# sqare_inch_challenge.net
KiCad netlist of a schematic drawn in EAGLE
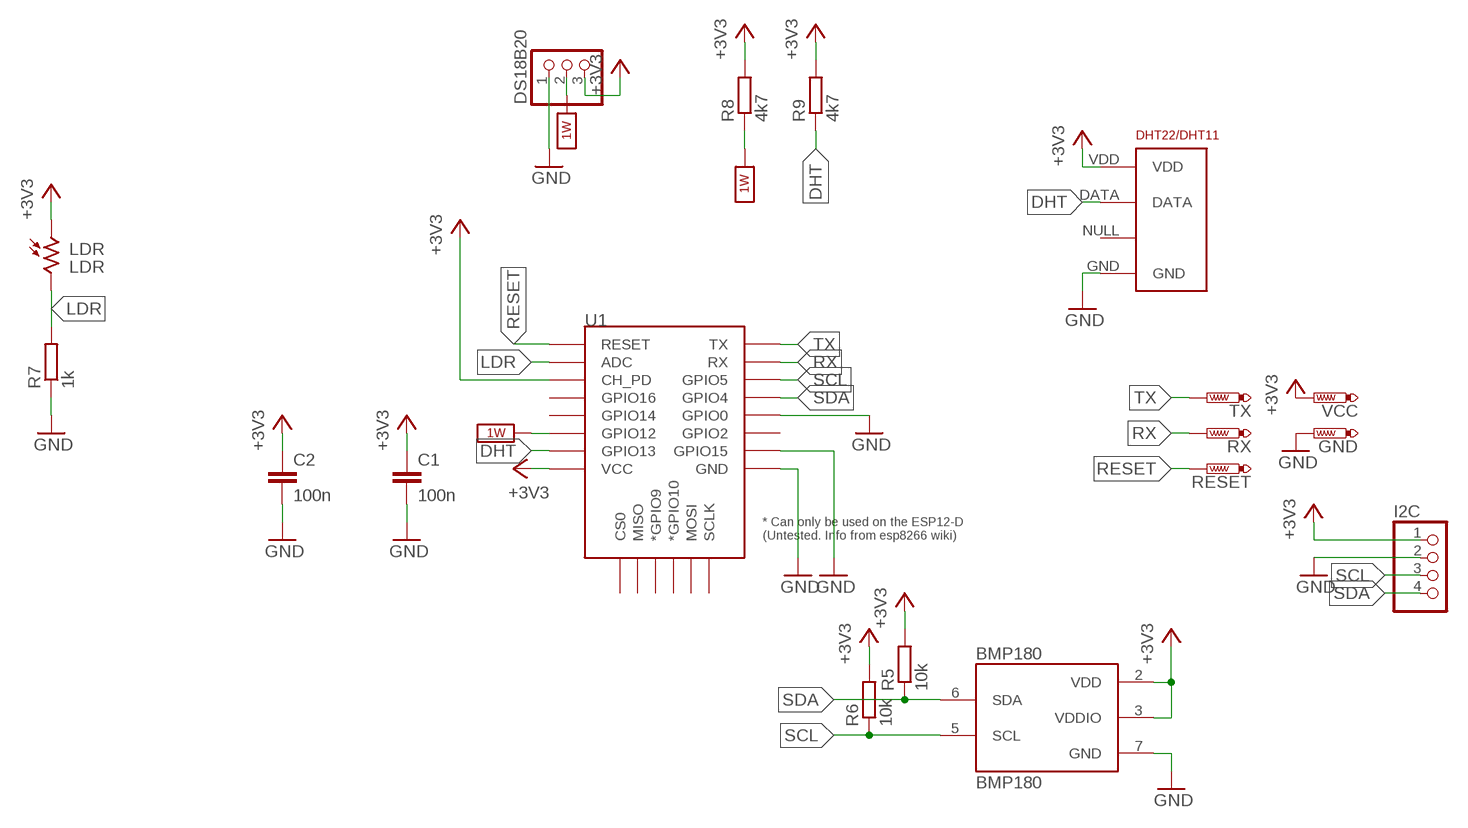
[diagram p0: schematic, sheet 1]

(export (version "E")
  (design (tool "Eeschema 10.0.6"))
  (components
    (comp (ref "BMP180")
      (value "BMP180")
      (footprint "eagle-import:BMP180")
      (libsource (lib "eagle-import") (part "BMP180"))
    )
    (comp (ref "C1")
      (value "100n")
      (footprint "eagle-import:C0805")
      (libsource (lib "eagle-import") (part "C-EUC0805"))
    )
    (comp (ref "C2")
      (value "100n")
      (footprint "eagle-import:C0805")
      (libsource (lib "eagle-import") (part "C-EUC0805"))
    )
    (comp (ref "DHT22/DHT11")
      (value "RHT03_DHT-22_AM2302")
      (footprint "eagle-import:RHT03_DHT-22")
      (libsource (lib "eagle-import") (part "RHT03_DHT-22_AM2302"))
    )
    (comp (ref "DS18B20")
      (value "PINHD-1X3")
      (footprint "eagle-import:1X03")
      (libsource (lib "eagle-import") (part "PINHD-1X3"))
    )
    (comp (ref "GND")
      (value "GND")
      (footprint "eagle-import:TP17SQ")
      (libsource (lib "eagle-import") (part "PTR1TP17SQ"))
    )
    (comp (ref "I2C")
      (value "PINHD-1X4")
      (footprint "eagle-import:1X04")
      (libsource (lib "eagle-import") (part "PINHD-1X4"))
    )
    (comp (ref "LDR")
      (value "LDR")
      (footprint "eagle-import:T0-46-A10XX")
      (libsource (lib "eagle-import") (part "A1050_13"))
    )
    (comp (ref "R5")
      (value "10k")
      (footprint "eagle-import:R0805")
      (libsource (lib "eagle-import") (part "R-EU_R0805"))
    )
    (comp (ref "R6")
      (value "10k")
      (footprint "eagle-import:R0805")
      (libsource (lib "eagle-import") (part "R-EU_R0805"))
    )
    (comp (ref "R7")
      (value "1k")
      (footprint "eagle-import:R0805")
      (libsource (lib "eagle-import") (part "R-EU_R0805"))
    )
    (comp (ref "R8")
      (value "4k7")
      (footprint "eagle-import:R0805")
      (libsource (lib "eagle-import") (part "R-EU_R0805"))
    )
    (comp (ref "R9")
      (value "4k7")
      (footprint "eagle-import:R0805")
      (libsource (lib "eagle-import") (part "R-EU_R0805"))
    )
    (comp (ref "RESET")
      (value "PTR1TP17SQ")
      (footprint "eagle-import:TP17SQ")
      (libsource (lib "eagle-import") (part "PTR1TP17SQ"))
    )
    (comp (ref "RX")
      (value "PTR1TP17SQ")
      (footprint "eagle-import:TP17SQ")
      (libsource (lib "eagle-import") (part "PTR1TP17SQ"))
    )
    (comp (ref "TX")
      (value "PTR1TP17SQ")
      (footprint "eagle-import:TP17SQ")
      (libsource (lib "eagle-import") (part "PTR1TP17SQ"))
    )
    (comp (ref "U1")
      (value "ESP12ESMD")
      (footprint "eagle-import:ESP12E-SMD")
      (libsource (lib "eagle-import") (part "ESP12ESMD"))
    )
    (comp (ref "VCC")
      (value "+3V3")
      (footprint "eagle-import:TP17SQ")
      (libsource (lib "eagle-import") (part "PTR1TP17SQ"))
    )
  )
  (nets
    (net (code "1") (name "+3V3") (class "Default")
      (node (ref "BMP180") (pin "2") (pinfunction "VDD_2") (pintype "power_in"))
      (node (ref "BMP180") (pin "3") (pinfunction "VDDIO_3") (pintype "power_in"))
      (node (ref "C1") (pin "1") (pinfunction "1_1") (pintype "passive"))
      (node (ref "C2") (pin "1") (pinfunction "1_1") (pintype "passive"))
      (node (ref "DHT22/DHT11") (pin "VDD") (pinfunction "VDD_VDD") (pintype "power_in"))
      (node (ref "DS18B20") (pin "3") (pinfunction "3_3") (pintype "passive"))
      (node (ref "I2C") (pin "1") (pinfunction "1_1") (pintype "passive"))
      (node (ref "LDR") (pin "1") (pinfunction "1_1") (pintype "passive"))
      (node (ref "R5") (pin "2") (pinfunction "2_2") (pintype "passive"))
      (node (ref "R6") (pin "2") (pinfunction "2_2") (pintype "passive"))
      (node (ref "R8") (pin "2") (pinfunction "2_2") (pintype "passive"))
      (node (ref "R9") (pin "2") (pinfunction "2_2") (pintype "passive"))
      (node (ref "U1") (pin "CH_PD") (pinfunction "CH_PD_CH_PD") (pintype "bidirectional"))
      (node (ref "U1") (pin "VCC") (pinfunction "VCC_VCC") (pintype "bidirectional"))
      (node (ref "VCC") (pin "TP") (pinfunction "TP_TP") (pintype "input"))
    )
    (net (code "2") (name "1W_SUP") (class "Default")
      (node (ref "DS18B20") (pin "2") (pinfunction "2_2") (pintype "passive"))
      (node (ref "R8") (pin "1") (pinfunction "1_1") (pintype "passive"))
      (node (ref "U1") (pin "GPIO12") (pinfunction "GPIO12_GPIO12") (pintype "bidirectional"))
    )
    (net (code "3") (name "DHT") (class "Default")
      (node (ref "DHT22/DHT11") (pin "DATA") (pinfunction "DATA_DATA") (pintype "bidirectional"))
      (node (ref "R9") (pin "1") (pinfunction "1_1") (pintype "passive"))
      (node (ref "U1") (pin "GPIO13") (pinfunction "GPIO13_GPIO13") (pintype "bidirectional"))
    )
    (net (code "4") (name "GND") (class "Default")
      (node (ref "BMP180") (pin "7") (pinfunction "GND_7") (pintype "power_in"))
      (node (ref "C1") (pin "2") (pinfunction "2_2") (pintype "passive"))
      (node (ref "C2") (pin "2") (pinfunction "2_2") (pintype "passive"))
      (node (ref "DHT22/DHT11") (pin "GND") (pinfunction "GND_GND") (pintype "power_in"))
      (node (ref "DS18B20") (pin "1") (pinfunction "1_1") (pintype "passive"))
      (node (ref "GND") (pin "TP") (pinfunction "TP_TP") (pintype "input"))
      (node (ref "I2C") (pin "2") (pinfunction "2_2") (pintype "passive"))
      (node (ref "R7") (pin "1") (pinfunction "1_1") (pintype "passive"))
      (node (ref "U1") (pin "GND") (pinfunction "GND_GND") (pintype "bidirectional"))
      (node (ref "U1") (pin "GPIO0") (pinfunction "GPIO0_GPIO0") (pintype "bidirectional"))
      (node (ref "U1") (pin "GPIO15") (pinfunction "GPIO15_GPIO15") (pintype "bidirectional"))
    )
    (net (code "5") (name "LDR") (class "Default")
      (node (ref "LDR") (pin "2") (pinfunction "2_2") (pintype "passive"))
      (node (ref "R7") (pin "2") (pinfunction "2_2") (pintype "passive"))
      (node (ref "U1") (pin "ADC") (pinfunction "ADC_ADC") (pintype "bidirectional"))
    )
    (net (code "6") (name "RESET") (class "Default")
      (node (ref "RESET") (pin "TP") (pinfunction "TP_TP") (pintype "input"))
      (node (ref "U1") (pin "RESET") (pinfunction "RESET_RESET") (pintype "bidirectional"))
    )
    (net (code "7") (name "RX") (class "Default")
      (node (ref "RX") (pin "TP") (pinfunction "TP_TP") (pintype "input"))
      (node (ref "U1") (pin "RXD0") (pinfunction "RX_RXD0") (pintype "bidirectional"))
    )
    (net (code "8") (name "SCL") (class "Default")
      (node (ref "BMP180") (pin "5") (pinfunction "SCL_5") (pintype "input"))
      (node (ref "I2C") (pin "3") (pinfunction "3_3") (pintype "passive"))
      (node (ref "R6") (pin "1") (pinfunction "1_1") (pintype "passive"))
      (node (ref "U1") (pin "GPIO5") (pinfunction "GPIO5_GPIO5") (pintype "bidirectional"))
    )
    (net (code "9") (name "SDA") (class "Default")
      (node (ref "BMP180") (pin "6") (pinfunction "SDA_6") (pintype "bidirectional"))
      (node (ref "I2C") (pin "4") (pinfunction "4_4") (pintype "passive"))
      (node (ref "R5") (pin "1") (pinfunction "1_1") (pintype "passive"))
      (node (ref "U1") (pin "GPIO4") (pinfunction "GPIO4_GPIO4") (pintype "bidirectional"))
    )
    (net (code "10") (name "TX") (class "Default")
      (node (ref "TX") (pin "TP") (pinfunction "TP_TP") (pintype "input"))
      (node (ref "U1") (pin "TXD0") (pinfunction "TX_TXD0") (pintype "bidirectional"))
    )
    (net (code "11") (name "unconnected-(DHT22/DHT11-PadNULL)") (class "Default")
      (node (ref "DHT22/DHT11") (pin "NULL") (pinfunction "NULL_NULL") (pintype "no_connect"))
    )
    (net (code "12") (name "unconnected-(U1-*GPIO9-PadGPIO9)") (class "Default")
      (node (ref "U1") (pin "GPIO9") (pinfunction "*GPIO9_GPIO9") (pintype "bidirectional"))
    )
    (net (code "13") (name "unconnected-(U1-*GPIO10-PadGPIO10)") (class "Default")
      (node (ref "U1") (pin "GPIO10") (pinfunction "*GPIO10_GPIO10") (pintype "bidirectional"))
    )
    (net (code "14") (name "unconnected-(U1-PadCS0)") (class "Default")
      (node (ref "U1") (pin "CS0") (pinfunction "CS0_CS0") (pintype "bidirectional"))
    )
    (net (code "15") (name "unconnected-(U1-PadGPIO2)") (class "Default")
      (node (ref "U1") (pin "GPIO2") (pinfunction "GPIO2_GPIO2") (pintype "bidirectional"))
    )
    (net (code "16") (name "unconnected-(U1-PadGPIO14)") (class "Default")
      (node (ref "U1") (pin "GPIO14") (pinfunction "GPIO14_GPIO14") (pintype "bidirectional"))
    )
    (net (code "17") (name "unconnected-(U1-PadGPIO16)") (class "Default")
      (node (ref "U1") (pin "GPIO16") (pinfunction "GPIO16_GPIO16") (pintype "bidirectional"))
    )
    (net (code "18") (name "unconnected-(U1-PadMISO)") (class "Default")
      (node (ref "U1") (pin "MISO") (pinfunction "MISO_MISO") (pintype "bidirectional"))
    )
    (net (code "19") (name "unconnected-(U1-PadMOSI)") (class "Default")
      (node (ref "U1") (pin "MOSI") (pinfunction "MOSI_MOSI") (pintype "bidirectional"))
    )
    (net (code "20") (name "unconnected-(U1-PadSCLK)") (class "Default")
      (node (ref "U1") (pin "SCLK") (pinfunction "SCLK_SCLK") (pintype "bidirectional"))
    )
  )
)
